# mirror-atmega8.net
KiCad netlist of a schematic drawn in EAGLE
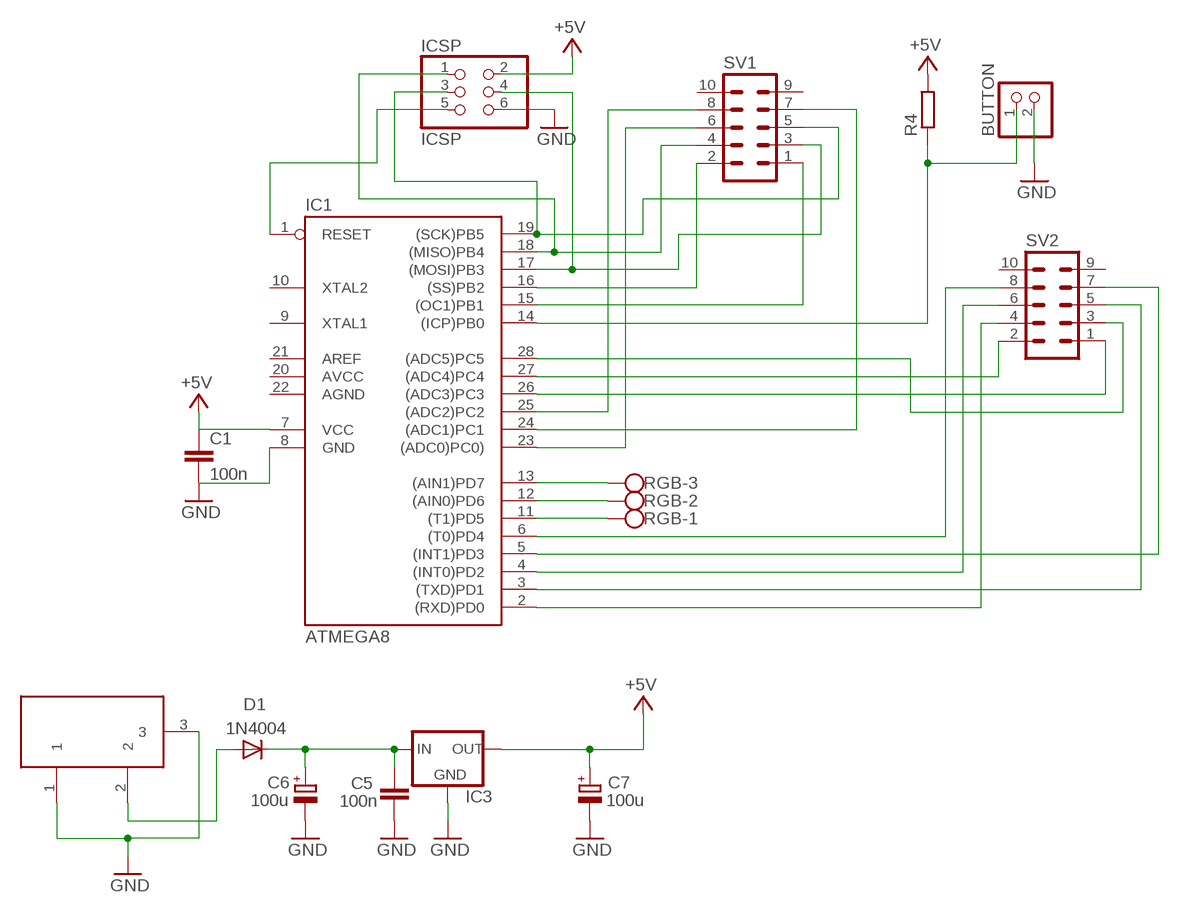
[diagram p0: schematic, sheet 1]

(export (version "E")
  (design (tool "Eeschema 10.0.6"))
  (components
    (comp (ref "BUTTON")
      (value "PINHD-1X2")
      (footprint "eagle-import:1X02")
      (libsource (lib "eagle-import") (part "PINHD-1X2"))
    )
    (comp (ref "C1")
      (value "100n")
      (footprint "eagle-import:C050-025X075")
      (libsource (lib "eagle-import") (part "C-EU050-025X075"))
    )
    (comp (ref "C5")
      (value "100n")
      (footprint "eagle-import:C050-025X075")
      (libsource (lib "eagle-import") (part "C-EU050-025X075"))
    )
    (comp (ref "C6")
      (value "100u")
      (footprint "eagle-import:E3,5-8")
      (libsource (lib "eagle-import") (part "CPOL-EUE3.5-8"))
    )
    (comp (ref "C7")
      (value "100u")
      (footprint "eagle-import:E3,5-8")
      (libsource (lib "eagle-import") (part "CPOL-EUE3.5-8"))
    )
    (comp (ref "D1")
      (value "1N4004")
      (footprint "eagle-import:DO41-10")
      (libsource (lib "eagle-import") (part "1N4004"))
    )
    (comp (ref "DC1")
      (value "DC21MMX")
      (footprint "eagle-import:DC-21MM")
      (libsource (lib "eagle-import") (part "DC21MMX"))
    )
    (comp (ref "IC1")
      (value "ATMEGA8")
      (footprint "eagle-import:DIL28-3")
      (libsource (lib "eagle-import") (part "AT90S4433P"))
    )
    (comp (ref "IC3")
      (value "78XXL")
      (footprint "eagle-import:78XXL")
      (libsource (lib "eagle-import") (part "78XXL"))
    )
    (comp (ref "ICSP")
      (value "ICSP")
      (footprint "eagle-import:2X03")
      (libsource (lib "eagle-import") (part "PINHD-2X3"))
    )
    (comp (ref "R4")
      (value "R-EU_0204/7")
      (footprint "eagle-import:0204_7")
      (libsource (lib "eagle-import") (part "R-EU_0204/7"))
    )
    (comp (ref "RGB")
      (value "W237-103")
      (footprint "eagle-import:W237-103")
      (libsource (lib "eagle-import") (part "W237-103"))
    )
    (comp (ref "SV1")
      (value "ML10")
      (footprint "eagle-import:ML10")
      (libsource (lib "eagle-import") (part "ML10"))
    )
    (comp (ref "SV2")
      (value "ML10")
      (footprint "eagle-import:ML10")
      (libsource (lib "eagle-import") (part "ML10"))
    )
  )
  (nets
    (net (code "1") (name "+5V") (class "Default")
      (node (ref "C1") (pin "1") (pinfunction "1_1") (pintype "passive"))
      (node (ref "C7") (pin "+") (pinfunction "+_+") (pintype "passive"))
      (node (ref "IC1") (pin "7") (pinfunction "VCC_7") (pintype "power_in"))
      (node (ref "IC3") (pin "OUT") (pinfunction "OUT_OUT") (pintype "passive"))
      (node (ref "ICSP") (pin "2") (pinfunction "2_2") (pintype "passive"))
      (node (ref "R4") (pin "2") (pinfunction "2_2") (pintype "passive"))
    )
    (net (code "2") (name "/AGND") (class "Default")
      (node (ref "IC1") (pin "22") (pinfunction "AGND_22") (pintype "power_in"))
    )
    (net (code "3") (name "/AREF") (class "Default")
      (node (ref "IC1") (pin "21") (pinfunction "AREF_21") (pintype "power_in"))
    )
    (net (code "4") (name "/AVCC") (class "Default")
      (node (ref "IC1") (pin "20") (pinfunction "AVCC_20") (pintype "power_in"))
    )
    (net (code "5") (name "GND") (class "Default")
      (node (ref "BUTTON") (pin "2") (pinfunction "2_2") (pintype "passive"))
      (node (ref "C1") (pin "2") (pinfunction "2_2") (pintype "passive"))
      (node (ref "C5") (pin "1") (pinfunction "1_1") (pintype "passive"))
      (node (ref "C6") (pin "-") (pinfunction "-_-") (pintype "passive"))
      (node (ref "C7") (pin "-") (pinfunction "-_-") (pintype "passive"))
      (node (ref "DC1") (pin "1") (pinfunction "1_1") (pintype "power_in"))
      (node (ref "DC1") (pin "3") (pinfunction "3_3") (pintype "power_in"))
      (node (ref "IC1") (pin "8") (pinfunction "GND_8") (pintype "power_in"))
      (node (ref "IC3") (pin "GND") (pinfunction "GND_GND") (pintype "input"))
      (node (ref "ICSP") (pin "6") (pinfunction "6_6") (pintype "passive"))
    )
    (net (code "6") (name "Net-(C5-Pad2)") (class "Default")
      (node (ref "C5") (pin "2") (pinfunction "2_2") (pintype "passive"))
      (node (ref "C6") (pin "+") (pinfunction "+_+") (pintype "passive"))
      (node (ref "D1") (pin "C") (pinfunction "C_C") (pintype "passive"))
      (node (ref "IC3") (pin "IN") (pinfunction "IN_IN") (pintype "input"))
    )
    (net (code "7") (name "Net-(D1-PadA)") (class "Default")
      (node (ref "D1") (pin "A") (pinfunction "A_A") (pintype "passive"))
      (node (ref "DC1") (pin "2") (pinfunction "2_2") (pintype "power_in"))
    )
    (net (code "8") (name "Net-(IC1-(ADC0)PC0))") (class "Default")
      (node (ref "IC1") (pin "23") (pinfunction "(ADC0)PC0)_23") (pintype "bidirectional"))
      (node (ref "SV1") (pin "6") (pinfunction "6_6") (pintype "passive"))
    )
    (net (code "9") (name "Net-(IC1-(ADC1)PC1)") (class "Default")
      (node (ref "IC1") (pin "24") (pinfunction "(ADC1)PC1_24") (pintype "bidirectional"))
      (node (ref "SV1") (pin "7") (pinfunction "7_7") (pintype "passive"))
    )
    (net (code "10") (name "Net-(IC1-(ADC2)PC2)") (class "Default")
      (node (ref "IC1") (pin "25") (pinfunction "(ADC2)PC2_25") (pintype "bidirectional"))
      (node (ref "SV1") (pin "8") (pinfunction "8_8") (pintype "passive"))
    )
    (net (code "11") (name "Net-(IC1-(ADC3)PC3)") (class "Default")
      (node (ref "IC1") (pin "26") (pinfunction "(ADC3)PC3_26") (pintype "bidirectional"))
      (node (ref "SV2") (pin "1") (pinfunction "1_1") (pintype "passive"))
    )
    (net (code "12") (name "Net-(IC1-(ADC4)PC4)") (class "Default")
      (node (ref "IC1") (pin "27") (pinfunction "(ADC4)PC4_27") (pintype "bidirectional"))
      (node (ref "SV2") (pin "2") (pinfunction "2_2") (pintype "passive"))
    )
    (net (code "13") (name "Net-(IC1-(ADC5)PC5)") (class "Default")
      (node (ref "IC1") (pin "28") (pinfunction "(ADC5)PC5_28") (pintype "bidirectional"))
      (node (ref "SV2") (pin "3") (pinfunction "3_3") (pintype "passive"))
    )
    (net (code "14") (name "Net-(IC1-(AIN0)PD6)") (class "Default")
      (node (ref "IC1") (pin "12") (pinfunction "(AIN0)PD6_12") (pintype "bidirectional"))
      (node (ref "RGB") (pin "2") (pinfunction "KL_2") (pintype "passive"))
    )
    (net (code "15") (name "Net-(IC1-(AIN1)PD7)") (class "Default")
      (node (ref "IC1") (pin "13") (pinfunction "(AIN1)PD7_13") (pintype "bidirectional"))
      (node (ref "RGB") (pin "3") (pinfunction "KL_3") (pintype "passive"))
    )
    (net (code "16") (name "Net-(IC1-(ICP)PB0)") (class "Default")
      (node (ref "BUTTON") (pin "1") (pinfunction "1_1") (pintype "passive"))
      (node (ref "IC1") (pin "14") (pinfunction "(ICP)PB0_14") (pintype "bidirectional"))
      (node (ref "R4") (pin "1") (pinfunction "1_1") (pintype "passive"))
    )
    (net (code "17") (name "Net-(IC1-(INT0)PD2)") (class "Default")
      (node (ref "IC1") (pin "4") (pinfunction "(INT0)PD2_4") (pintype "bidirectional"))
      (node (ref "SV2") (pin "6") (pinfunction "6_6") (pintype "passive"))
    )
    (net (code "18") (name "Net-(IC1-(INT1)PD3)") (class "Default")
      (node (ref "IC1") (pin "5") (pinfunction "(INT1)PD3_5") (pintype "bidirectional"))
      (node (ref "SV2") (pin "7") (pinfunction "7_7") (pintype "passive"))
    )
    (net (code "19") (name "Net-(IC1-(MISO)PB4)") (class "Default")
      (node (ref "IC1") (pin "18") (pinfunction "(MISO)PB4_18") (pintype "bidirectional"))
      (node (ref "ICSP") (pin "1") (pinfunction "1_1") (pintype "passive"))
      (node (ref "SV1") (pin "4") (pinfunction "4_4") (pintype "passive"))
    )
    (net (code "20") (name "Net-(IC1-(MOSI)PB3)") (class "Default")
      (node (ref "IC1") (pin "17") (pinfunction "(MOSI)PB3_17") (pintype "bidirectional"))
      (node (ref "ICSP") (pin "4") (pinfunction "4_4") (pintype "passive"))
      (node (ref "SV1") (pin "3") (pinfunction "3_3") (pintype "passive"))
    )
    (net (code "21") (name "Net-(IC1-(OC1)PB1)") (class "Default")
      (node (ref "IC1") (pin "15") (pinfunction "(OC1)PB1_15") (pintype "bidirectional"))
      (node (ref "SV1") (pin "1") (pinfunction "1_1") (pintype "passive"))
    )
    (net (code "22") (name "Net-(IC1-(RXD)PD0)") (class "Default")
      (node (ref "IC1") (pin "2") (pinfunction "(RXD)PD0_2") (pintype "bidirectional"))
      (node (ref "SV2") (pin "4") (pinfunction "4_4") (pintype "passive"))
    )
    (net (code "23") (name "Net-(IC1-(SCK)PB5)") (class "Default")
      (node (ref "IC1") (pin "19") (pinfunction "(SCK)PB5_19") (pintype "bidirectional"))
      (node (ref "ICSP") (pin "3") (pinfunction "3_3") (pintype "passive"))
      (node (ref "SV1") (pin "5") (pinfunction "5_5") (pintype "passive"))
    )
    (net (code "24") (name "Net-(IC1-(SS)PB2)") (class "Default")
      (node (ref "IC1") (pin "16") (pinfunction "(SS)PB2_16") (pintype "bidirectional"))
      (node (ref "SV1") (pin "2") (pinfunction "2_2") (pintype "passive"))
    )
    (net (code "25") (name "Net-(IC1-(T0)PD4)") (class "Default")
      (node (ref "IC1") (pin "6") (pinfunction "(T0)PD4_6") (pintype "bidirectional"))
      (node (ref "SV2") (pin "8") (pinfunction "8_8") (pintype "passive"))
    )
    (net (code "26") (name "Net-(IC1-(T1)PD5)") (class "Default")
      (node (ref "IC1") (pin "11") (pinfunction "(T1)PD5_11") (pintype "bidirectional"))
      (node (ref "RGB") (pin "1") (pinfunction "KL_1") (pintype "passive"))
    )
    (net (code "27") (name "Net-(IC1-(TXD)PD1)") (class "Default")
      (node (ref "IC1") (pin "3") (pinfunction "(TXD)PD1_3") (pintype "bidirectional"))
      (node (ref "SV2") (pin "5") (pinfunction "5_5") (pintype "passive"))
    )
    (net (code "28") (name "Net-(IC1-RESET)") (class "Default")
      (node (ref "IC1") (pin "1") (pinfunction "RESET_1") (pintype "input"))
      (node (ref "ICSP") (pin "5") (pinfunction "5_5") (pintype "passive"))
    )
    (net (code "29") (name "unconnected-(IC1-XTAL1-Pad9)") (class "Default")
      (node (ref "IC1") (pin "9") (pinfunction "XTAL1_9") (pintype "bidirectional"))
    )
    (net (code "30") (name "unconnected-(IC1-XTAL2-Pad10)") (class "Default")
      (node (ref "IC1") (pin "10") (pinfunction "XTAL2_10") (pintype "bidirectional"))
    )
    (net (code "31") (name "unconnected-(SV1-Pad9)") (class "Default")
      (node (ref "SV1") (pin "9") (pinfunction "9_9") (pintype "passive"))
    )
    (net (code "32") (name "unconnected-(SV1-Pad10)") (class "Default")
      (node (ref "SV1") (pin "10") (pinfunction "10_10") (pintype "passive"))
    )
    (net (code "33") (name "unconnected-(SV2-Pad9)") (class "Default")
      (node (ref "SV2") (pin "9") (pinfunction "9_9") (pintype "passive"))
    )
    (net (code "34") (name "unconnected-(SV2-Pad10)") (class "Default")
      (node (ref "SV2") (pin "10") (pinfunction "10_10") (pintype "passive"))
    )
  )
)
